# CanSatPrimaria.net
KiCad netlist of a schematic drawn in EAGLE
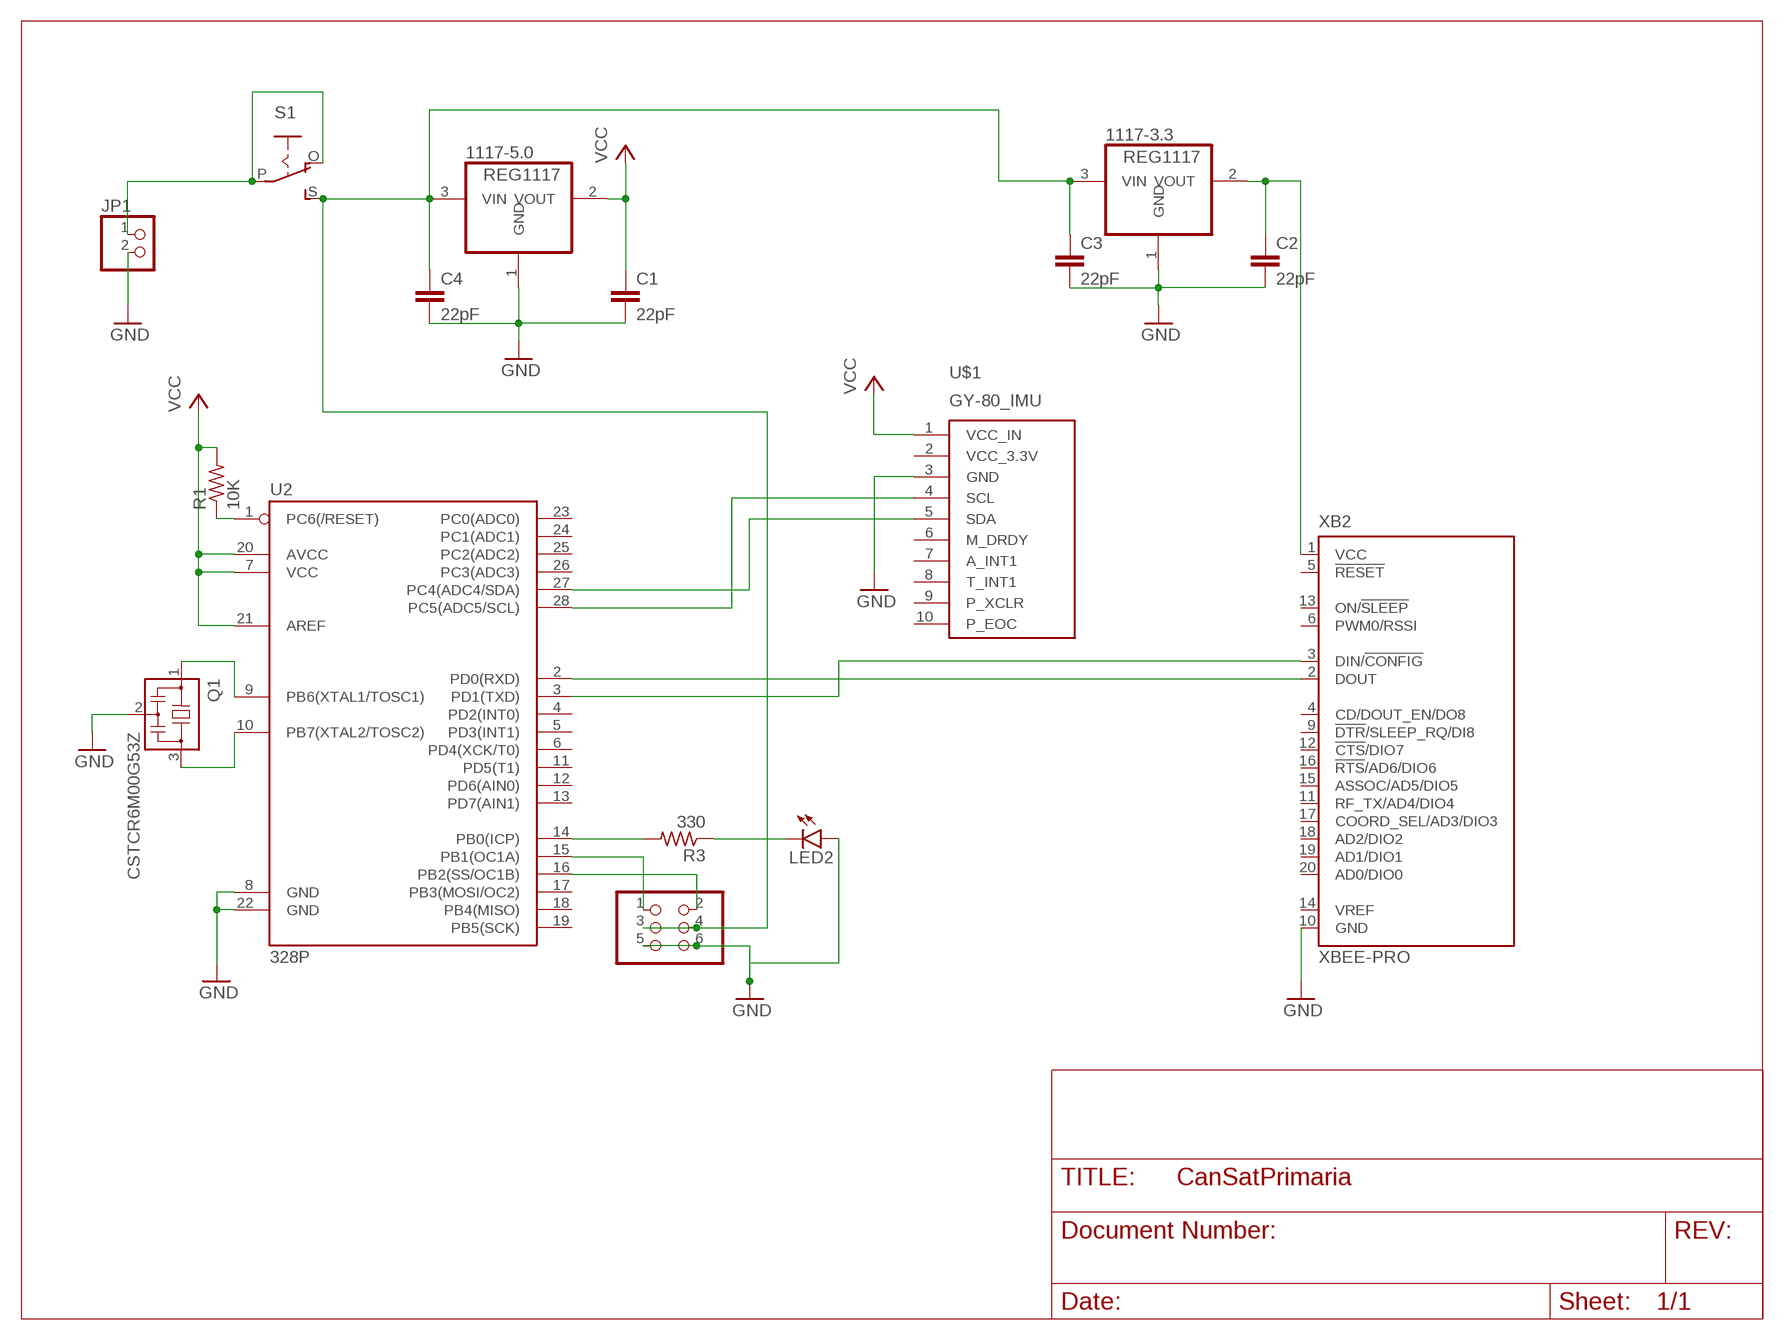
[diagram p0: schematic, sheet 1]

(export (version "E")
  (design (tool "Eeschema 10.0.6"))
  (components
    (comp (ref "1117-3.3")
      (value "REG1117")
      (footprint "eagle-import:SOT223")
      (libsource (lib "eagle-import") (part "REG1117"))
    )
    (comp (ref "1117-5.0")
      (value "REG1117")
      (footprint "eagle-import:SOT223")
      (libsource (lib "eagle-import") (part "REG1117"))
    )
    (comp (ref "C1")
      (value "22pF")
      (footprint "eagle-import:C1206")
      (libsource (lib "eagle-import") (part "C-EUC1206"))
    )
    (comp (ref "C2")
      (value "22pF")
      (footprint "eagle-import:C1206")
      (libsource (lib "eagle-import") (part "C-EUC1206"))
    )
    (comp (ref "C3")
      (value "22pF")
      (footprint "eagle-import:C1206")
      (libsource (lib "eagle-import") (part "C-EUC1206"))
    )
    (comp (ref "C4")
      (value "22pF")
      (footprint "eagle-import:C1206")
      (libsource (lib "eagle-import") (part "C-EUC1206"))
    )
    (comp (ref "JP1")
      (value "PINHD-1X2")
      (footprint "eagle-import:1X02")
      (libsource (lib "eagle-import") (part "PINHD-1X2"))
    )
    (comp (ref "JP3")
      (value "PINHD-2X3")
      (footprint "eagle-import:2X03")
      (libsource (lib "eagle-import") (part "PINHD-2X3"))
    )
    (comp (ref "LED2")
      (value "LEDCHIPLED_1206")
      (footprint "eagle-import:CHIPLED_1206")
      (libsource (lib "eagle-import") (part "LEDCHIPLED_1206"))
    )
    (comp (ref "Q1")
      (value "CSTCR6M00G53Z")
      (footprint "eagle-import:CSTCR6M")
      (fields (field (name "MPN") "CSTCR6M00G53-R0"))
      (libsource (lib "eagle-import") (part "CSTCR6M00G53Z"))
    )
    (comp (ref "R1")
      (value "10K")
      (footprint "eagle-import:M1206")
      (libsource (lib "eagle-import") (part "R-US_M1206"))
    )
    (comp (ref "R3")
      (value "330")
      (footprint "eagle-import:M1206")
      (libsource (lib "eagle-import") (part "R-US_M1206"))
    )
    (comp (ref "S1")
      (value "EG1218S")
      (footprint "eagle-import:EG1218")
      (libsource (lib "eagle-import") (part "EG1218S"))
    )
    (comp (ref "U$1")
      (value "GY-80_IMU")
      (footprint "eagle-import:MA10-1")
      (libsource (lib "eagle-import") (part "GY-80_IMU"))
    )
    (comp (ref "U2")
      (value "328P")
      (footprint "eagle-import:DIP28")
      (libsource (lib "eagle-import") (part "ATMEGA328P_PDIP"))
    )
    (comp (ref "XB2")
      (value "XBEE-PRO")
      (footprint "eagle-import:XBEE-PRO")
      (fields (field (name "MPN") "XBP24-AWI-001"))
      (libsource (lib "eagle-import") (part "XBEE-PRO"))
    )
  )
  (nets
    (net (code "1") (name "GND") (class "Default")
      (node (ref "1117-3.3") (pin "1") (pinfunction "GND_1") (pintype "power_in"))
      (node (ref "1117-5.0") (pin "1") (pinfunction "GND_1") (pintype "power_in"))
      (node (ref "C1") (pin "2") (pinfunction "2_2") (pintype "passive"))
      (node (ref "C2") (pin "2") (pinfunction "2_2") (pintype "passive"))
      (node (ref "C3") (pin "2") (pinfunction "2_2") (pintype "passive"))
      (node (ref "C4") (pin "2") (pinfunction "2_2") (pintype "passive"))
      (node (ref "JP1") (pin "2") (pinfunction "2_2") (pintype "passive"))
      (node (ref "JP3") (pin "5") (pinfunction "5_5") (pintype "passive"))
      (node (ref "JP3") (pin "6") (pinfunction "6_6") (pintype "passive"))
      (node (ref "LED2") (pin "A") (pinfunction "A_A") (pintype "passive"))
      (node (ref "Q1") (pin "2") (pinfunction "2_2") (pintype "passive"))
      (node (ref "U$1") (pin "3") (pinfunction "GND_3") (pintype "bidirectional"))
      (node (ref "U2") (pin "22") (pinfunction "GND_22") (pintype "bidirectional"))
      (node (ref "U2") (pin "8") (pinfunction "GND_8") (pintype "bidirectional"))
      (node (ref "XB2") (pin "10") (pinfunction "GND_10") (pintype "power_in"))
    )
    (net (code "2") (name "Net-(1117-3.3-VIN)") (class "Default")
      (node (ref "1117-3.3") (pin "3") (pinfunction "VIN_3") (pintype "input"))
      (node (ref "1117-5.0") (pin "3") (pinfunction "VIN_3") (pintype "input"))
      (node (ref "C3") (pin "1") (pinfunction "1_1") (pintype "passive"))
      (node (ref "C4") (pin "1") (pinfunction "1_1") (pintype "passive"))
      (node (ref "JP3") (pin "3") (pinfunction "3_3") (pintype "passive"))
      (node (ref "JP3") (pin "4") (pinfunction "4_4") (pintype "passive"))
      (node (ref "S1") (pin "S") (pinfunction "S_S") (pintype "passive"))
    )
    (net (code "3") (name "Net-(1117-3.3-VOUT)") (class "Default")
      (node (ref "1117-3.3") (pin "2") (pinfunction "VOUT_2") (pintype "output"))
      (node (ref "C2") (pin "1") (pinfunction "1_1") (pintype "passive"))
      (node (ref "XB2") (pin "1") (pinfunction "VCC_1") (pintype "power_in"))
    )
    (net (code "4") (name "Net-(JP1-Pad1)") (class "Default")
      (node (ref "JP1") (pin "1") (pinfunction "1_1") (pintype "passive"))
      (node (ref "S1") (pin "O") (pinfunction "O_O") (pintype "passive"))
      (node (ref "S1") (pin "P") (pinfunction "P_P") (pintype "passive"))
    )
    (net (code "5") (name "Net-(LED2-PadC)") (class "Default")
      (node (ref "LED2") (pin "C") (pinfunction "C_C") (pintype "passive"))
      (node (ref "R3") (pin "1") (pinfunction "1_1") (pintype "passive"))
    )
    (net (code "6") (name "Net-(U$1-SCL)") (class "Default")
      (node (ref "U$1") (pin "4") (pinfunction "SCL_4") (pintype "bidirectional"))
      (node (ref "U2") (pin "28") (pinfunction "PC5(ADC5/SCL)_28") (pintype "bidirectional"))
    )
    (net (code "7") (name "Net-(U$1-SDA)") (class "Default")
      (node (ref "U$1") (pin "5") (pinfunction "SDA_5") (pintype "bidirectional"))
      (node (ref "U2") (pin "27") (pinfunction "PC4(ADC4/SDA)_27") (pintype "bidirectional"))
    )
    (net (code "8") (name "Net-(U2-PB0(ICP))") (class "Default")
      (node (ref "R3") (pin "2") (pinfunction "2_2") (pintype "passive"))
      (node (ref "U2") (pin "14") (pinfunction "PB0(ICP)_14") (pintype "bidirectional"))
    )
    (net (code "9") (name "Net-(U2-PB1(OC1A))") (class "Default")
      (node (ref "JP3") (pin "1") (pinfunction "1_1") (pintype "passive"))
      (node (ref "U2") (pin "15") (pinfunction "PB1(OC1A)_15") (pintype "bidirectional"))
    )
    (net (code "10") (name "Net-(U2-PB2(SS{slash}OC1B))") (class "Default")
      (node (ref "JP3") (pin "2") (pinfunction "2_2") (pintype "passive"))
      (node (ref "U2") (pin "16") (pinfunction "PB2(SS/OC1B)_16") (pintype "bidirectional"))
    )
    (net (code "11") (name "Net-(U2-PB6(XTAL1{slash}TOSC1))") (class "Default")
      (node (ref "Q1") (pin "1") (pinfunction "1_1") (pintype "passive"))
      (node (ref "U2") (pin "9") (pinfunction "PB6(XTAL1/TOSC1)_9") (pintype "bidirectional"))
    )
    (net (code "12") (name "Net-(U2-PB7(XTAL2{slash}TOSC2))") (class "Default")
      (node (ref "Q1") (pin "3") (pinfunction "3_3") (pintype "passive"))
      (node (ref "U2") (pin "10") (pinfunction "PB7(XTAL2/TOSC2)_10") (pintype "bidirectional"))
    )
    (net (code "13") (name "Net-(U2-PC6({slash}RESET))") (class "Default")
      (node (ref "R1") (pin "1") (pinfunction "1_1") (pintype "passive"))
      (node (ref "U2") (pin "1") (pinfunction "PC6(/RESET)_1") (pintype "bidirectional"))
    )
    (net (code "14") (name "Net-(U2-PD0(RXD))") (class "Default")
      (node (ref "U2") (pin "2") (pinfunction "PD0(RXD)_2") (pintype "bidirectional"))
      (node (ref "XB2") (pin "2") (pinfunction "DOUT_2") (pintype "output"))
    )
    (net (code "15") (name "Net-(U2-PD1(TXD))") (class "Default")
      (node (ref "U2") (pin "3") (pinfunction "PD1(TXD)_3") (pintype "bidirectional"))
      (node (ref "XB2") (pin "3") (pinfunction "DIN/~{CONFIG}_3") (pintype "input"))
    )
    (net (code "16") (name "VCC") (class "Default")
      (node (ref "1117-5.0") (pin "2") (pinfunction "VOUT_2") (pintype "output"))
      (node (ref "C1") (pin "1") (pinfunction "1_1") (pintype "passive"))
      (node (ref "R1") (pin "2") (pinfunction "2_2") (pintype "passive"))
      (node (ref "U$1") (pin "1") (pinfunction "VCC_IN_1") (pintype "bidirectional"))
      (node (ref "U2") (pin "20") (pinfunction "AVCC_20") (pintype "bidirectional"))
      (node (ref "U2") (pin "21") (pinfunction "AREF_21") (pintype "bidirectional"))
      (node (ref "U2") (pin "7") (pinfunction "VCC_7") (pintype "bidirectional"))
    )
    (net (code "17") (name "unconnected-(U$1-A_INT1-Pad7)") (class "Default")
      (node (ref "U$1") (pin "7") (pinfunction "A_INT1_7") (pintype "bidirectional"))
    )
    (net (code "18") (name "unconnected-(U$1-M_DRDY-Pad6)") (class "Default")
      (node (ref "U$1") (pin "6") (pinfunction "M_DRDY_6") (pintype "bidirectional"))
    )
    (net (code "19") (name "unconnected-(U$1-P_EOC-Pad10)") (class "Default")
      (node (ref "U$1") (pin "10") (pinfunction "P_EOC_10") (pintype "bidirectional"))
    )
    (net (code "20") (name "unconnected-(U$1-P_XCLR-Pad9)") (class "Default")
      (node (ref "U$1") (pin "9") (pinfunction "P_XCLR_9") (pintype "bidirectional"))
    )
    (net (code "21") (name "unconnected-(U$1-T_INT1-Pad8)") (class "Default")
      (node (ref "U$1") (pin "8") (pinfunction "T_INT1_8") (pintype "bidirectional"))
    )
    (net (code "22") (name "unconnected-(U$1-VCC_3.3V-Pad2)") (class "Default")
      (node (ref "U$1") (pin "2") (pinfunction "VCC_3.3V_2") (pintype "bidirectional"))
    )
    (net (code "23") (name "unconnected-(U2-PB3(MOSI{slash}OC2)-Pad17)") (class "Default")
      (node (ref "U2") (pin "17") (pinfunction "PB3(MOSI/OC2)_17") (pintype "bidirectional"))
    )
    (net (code "24") (name "unconnected-(U2-PB4(MISO)-Pad18)") (class "Default")
      (node (ref "U2") (pin "18") (pinfunction "PB4(MISO)_18") (pintype "bidirectional"))
    )
    (net (code "25") (name "unconnected-(U2-PB5(SCK)-Pad19)") (class "Default")
      (node (ref "U2") (pin "19") (pinfunction "PB5(SCK)_19") (pintype "bidirectional"))
    )
    (net (code "26") (name "unconnected-(U2-PC0(ADC0)-Pad23)") (class "Default")
      (node (ref "U2") (pin "23") (pinfunction "PC0(ADC0)_23") (pintype "bidirectional"))
    )
    (net (code "27") (name "unconnected-(U2-PC1(ADC1)-Pad24)") (class "Default")
      (node (ref "U2") (pin "24") (pinfunction "PC1(ADC1)_24") (pintype "bidirectional"))
    )
    (net (code "28") (name "unconnected-(U2-PC2(ADC2)-Pad25)") (class "Default")
      (node (ref "U2") (pin "25") (pinfunction "PC2(ADC2)_25") (pintype "bidirectional"))
    )
    (net (code "29") (name "unconnected-(U2-PC3(ADC3)-Pad26)") (class "Default")
      (node (ref "U2") (pin "26") (pinfunction "PC3(ADC3)_26") (pintype "bidirectional"))
    )
    (net (code "30") (name "unconnected-(U2-PD2(INT0)-Pad4)") (class "Default")
      (node (ref "U2") (pin "4") (pinfunction "PD2(INT0)_4") (pintype "bidirectional"))
    )
    (net (code "31") (name "unconnected-(U2-PD3(INT1)-Pad5)") (class "Default")
      (node (ref "U2") (pin "5") (pinfunction "PD3(INT1)_5") (pintype "bidirectional"))
    )
    (net (code "32") (name "unconnected-(U2-PD4(XCK{slash}T0)-Pad6)") (class "Default")
      (node (ref "U2") (pin "6") (pinfunction "PD4(XCK/T0)_6") (pintype "bidirectional"))
    )
    (net (code "33") (name "unconnected-(U2-PD5(T1)-Pad11)") (class "Default")
      (node (ref "U2") (pin "11") (pinfunction "PD5(T1)_11") (pintype "bidirectional"))
    )
    (net (code "34") (name "unconnected-(U2-PD6(AIN0)-Pad12)") (class "Default")
      (node (ref "U2") (pin "12") (pinfunction "PD6(AIN0)_12") (pintype "bidirectional"))
    )
    (net (code "35") (name "unconnected-(U2-PD7(AIN1)-Pad13)") (class "Default")
      (node (ref "U2") (pin "13") (pinfunction "PD7(AIN1)_13") (pintype "bidirectional"))
    )
    (net (code "36") (name "unconnected-(XB2-AD0{slash}DIO0-Pad20)") (class "Default")
      (node (ref "XB2") (pin "20") (pinfunction "AD0/DIO0_20") (pintype "bidirectional"))
    )
    (net (code "37") (name "unconnected-(XB2-AD1{slash}DIO1-Pad19)") (class "Default")
      (node (ref "XB2") (pin "19") (pinfunction "AD1/DIO1_19") (pintype "bidirectional"))
    )
    (net (code "38") (name "unconnected-(XB2-AD2{slash}DIO2-Pad18)") (class "Default")
      (node (ref "XB2") (pin "18") (pinfunction "AD2/DIO2_18") (pintype "bidirectional"))
    )
    (net (code "39") (name "unconnected-(XB2-ASSOC{slash}AD5{slash}DIO5-Pad15)") (class "Default")
      (node (ref "XB2") (pin "15") (pinfunction "ASSOC/AD5/DIO5_15") (pintype "bidirectional"))
    )
    (net (code "40") (name "unconnected-(XB2-CD{slash}DOUT_EN{slash}DO8-Pad4)") (class "Default")
      (node (ref "XB2") (pin "4") (pinfunction "CD/DOUT_EN/DO8_4") (pintype "output"))
    )
    (net (code "41") (name "unconnected-(XB2-COORD_SEL{slash}AD3{slash}DIO3-Pad17)") (class "Default")
      (node (ref "XB2") (pin "17") (pinfunction "COORD_SEL/AD3/DIO3_17") (pintype "bidirectional"))
    )
    (net (code "42") (name "unconnected-(XB2-ON{slash}~{SLEEP}-Pad13)") (class "Default")
      (node (ref "XB2") (pin "13") (pinfunction "ON/~{SLEEP}_13") (pintype "output"))
    )
    (net (code "43") (name "unconnected-(XB2-PWM0{slash}RSSI-Pad6)") (class "Default")
      (node (ref "XB2") (pin "6") (pinfunction "PWM0/RSSI_6") (pintype "output"))
    )
    (net (code "44") (name "unconnected-(XB2-RF_TX{slash}AD4{slash}DIO4-Pad11)") (class "Default")
      (node (ref "XB2") (pin "11") (pinfunction "RF_TX/AD4/DIO4_11") (pintype "bidirectional"))
    )
    (net (code "45") (name "unconnected-(XB2-VREF-Pad14)") (class "Default")
      (node (ref "XB2") (pin "14") (pinfunction "VREF_14") (pintype "input"))
    )
    (net (code "46") (name "unconnected-(XB2-~{CTS}{slash}DIO7-Pad12)") (class "Default")
      (node (ref "XB2") (pin "12") (pinfunction "~{CTS}/DIO7_12") (pintype "bidirectional"))
    )
    (net (code "47") (name "unconnected-(XB2-~{DTR}{slash}SLEEP_RQ{slash}DI8-Pad9)") (class "Default")
      (node (ref "XB2") (pin "9") (pinfunction "~{DTR}/SLEEP_RQ/DI8_9") (pintype "bidirectional"))
    )
    (net (code "48") (name "unconnected-(XB2-~{RESET}-Pad5)") (class "Default")
      (node (ref "XB2") (pin "5") (pinfunction "~{RESET}_5") (pintype "input"))
    )
    (net (code "49") (name "unconnected-(XB2-~{RTS}{slash}AD6{slash}DIO6-Pad16)") (class "Default")
      (node (ref "XB2") (pin "16") (pinfunction "~{RTS}/AD6/DIO6_16") (pintype "bidirectional"))
    )
  )
)
